# PWR_Gen.net
KiCad netlist of a schematic drawn in Altium Designer
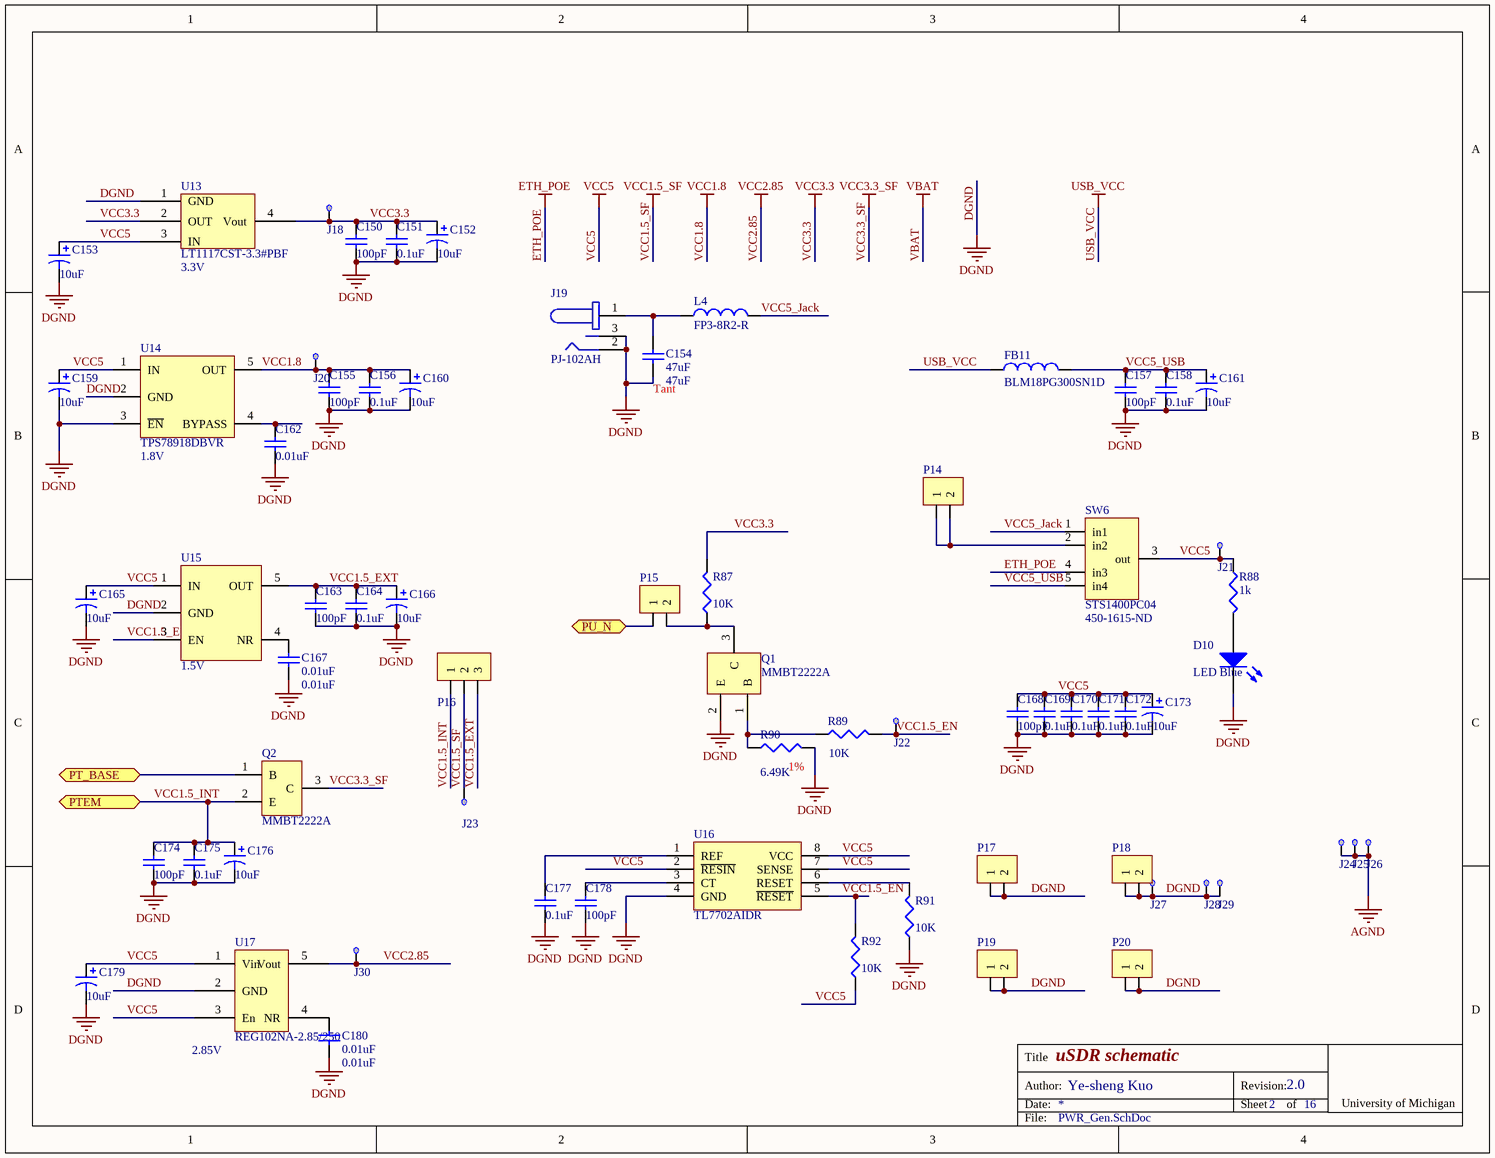
[diagram p0: PWR_Gen.SchDoc]

(export (version "E")
  (design (tool "Eeschema 10.0.6"))
  (components
    (comp (ref "C150")
      (value "100pF")
      (footprint "0402")
      (description "Capacitor (Semiconductor SIM Model)")
      (fields (field (name "PUBLISHER") "Altium Limited"))
      (libsource (lib "Miscellaneous Devices") (part "Cap Semi"))
    )
    (comp (ref "C151")
      (value "0.1uF")
      (footprint "0402")
      (description "Capacitor (Semiconductor SIM Model)")
      (fields (field (name "PUBLISHER") "Altium Limited"))
      (libsource (lib "Miscellaneous Devices") (part "Cap Semi"))
    )
    (comp (ref "C152")
      (value "10uF")
      (footprint "C0805")
      (description "Polarized Capacitor (Surface Mount)")
      (fields (field (name "PUBLISHER") "Altium Limited"))
      (libsource (lib "Miscellaneous Devices") (part "Cap Pol3"))
    )
    (comp (ref "C153")
      (value "10uF")
      (footprint "C0805")
      (description "Polarized Capacitor (Surface Mount)")
      (fields (field (name "PUBLISHER") "Altium Limited"))
      (libsource (lib "Miscellaneous Devices") (part "Cap Pol3"))
    )
    (comp (ref "C154")
      (value "47uF")
      (footprint "C1210")
      (description "Capacitor (Semiconductor SIM Model)")
      (fields (field (name "ALTIUM_VALUE") "47uF") (field (name "PUBLISHER") "Altium Limited"))
      (libsource (lib "Miscellaneous Devices") (part "Cap Semi"))
    )
    (comp (ref "C155")
      (value "100pF")
      (footprint "0402")
      (description "Capacitor (Semiconductor SIM Model)")
      (fields (field (name "PUBLISHER") "Altium Limited"))
      (libsource (lib "Miscellaneous Devices") (part "Cap Semi"))
    )
    (comp (ref "C156")
      (value "0.1uF")
      (footprint "0402")
      (description "Capacitor (Semiconductor SIM Model)")
      (fields (field (name "PUBLISHER") "Altium Limited"))
      (libsource (lib "Miscellaneous Devices") (part "Cap Semi"))
    )
    (comp (ref "C157")
      (value "100pF")
      (footprint "0402")
      (description "Capacitor (Semiconductor SIM Model)")
      (fields (field (name "PUBLISHER") "Altium Limited"))
      (libsource (lib "Miscellaneous Devices") (part "Cap Semi"))
    )
    (comp (ref "C158")
      (value "0.1uF")
      (footprint "0402")
      (description "Capacitor (Semiconductor SIM Model)")
      (fields (field (name "PUBLISHER") "Altium Limited"))
      (libsource (lib "Miscellaneous Devices") (part "Cap Semi"))
    )
    (comp (ref "C159")
      (value "10uF")
      (footprint "C0805")
      (description "Polarized Capacitor (Surface Mount)")
      (fields (field (name "PUBLISHER") "Altium Limited"))
      (libsource (lib "Miscellaneous Devices") (part "Cap Pol3"))
    )
    (comp (ref "C160")
      (value "10uF")
      (footprint "C0805")
      (description "Polarized Capacitor (Surface Mount)")
      (fields (field (name "PUBLISHER") "Altium Limited"))
      (libsource (lib "Miscellaneous Devices") (part "Cap Pol3"))
    )
    (comp (ref "C161")
      (value "10uF")
      (footprint "C0805")
      (description "Polarized Capacitor (Surface Mount)")
      (fields (field (name "PUBLISHER") "Altium Limited"))
      (libsource (lib "Miscellaneous Devices") (part "Cap Pol3"))
    )
    (comp (ref "C162")
      (value "0.01uF")
      (footprint "0402")
      (description "Capacitor (Semiconductor SIM Model)")
      (fields (field (name "PUBLISHER") "Altium Limited"))
      (libsource (lib "Miscellaneous Devices") (part "Cap Semi"))
    )
    (comp (ref "C163")
      (value "100pF")
      (footprint "0402")
      (description "Capacitor (Semiconductor SIM Model)")
      (fields (field (name "PUBLISHER") "Altium Limited"))
      (libsource (lib "Miscellaneous Devices") (part "Cap Semi"))
    )
    (comp (ref "C164")
      (value "0.1uF")
      (footprint "0402")
      (description "Capacitor (Semiconductor SIM Model)")
      (fields (field (name "PUBLISHER") "Altium Limited"))
      (libsource (lib "Miscellaneous Devices") (part "Cap Semi"))
    )
    (comp (ref "C165")
      (value "10uF")
      (footprint "C0805")
      (description "Polarized Capacitor (Surface Mount)")
      (fields (field (name "PUBLISHER") "Altium Limited"))
      (libsource (lib "Miscellaneous Devices") (part "Cap Pol3"))
    )
    (comp (ref "C166")
      (value "10uF")
      (footprint "C0805")
      (description "Polarized Capacitor (Surface Mount)")
      (fields (field (name "PUBLISHER") "Altium Limited"))
      (libsource (lib "Miscellaneous Devices") (part "Cap Pol3"))
    )
    (comp (ref "C167")
      (value "0.01uF")
      (footprint "0402")
      (description "Capacitor (Semiconductor SIM Model)")
      (fields (field (name "ALTIUM_VALUE") "0.01uF") (field (name "PUBLISHER") "Altium Limited"))
      (libsource (lib "Miscellaneous Devices") (part "Cap Semi"))
    )
    (comp (ref "C168")
      (value "100pF")
      (footprint "0402")
      (description "Capacitor (Semiconductor SIM Model)")
      (fields (field (name "PUBLISHER") "Altium Limited"))
      (libsource (lib "Miscellaneous Devices") (part "Cap Semi"))
    )
    (comp (ref "C169")
      (value "0.1uF")
      (footprint "0402")
      (description "Capacitor (Semiconductor SIM Model)")
      (fields (field (name "PUBLISHER") "Altium Limited"))
      (libsource (lib "Miscellaneous Devices") (part "Cap Semi"))
    )
    (comp (ref "C170")
      (value "0.1uF")
      (footprint "0402")
      (description "Capacitor (Semiconductor SIM Model)")
      (fields (field (name "PUBLISHER") "Altium Limited"))
      (libsource (lib "Miscellaneous Devices") (part "Cap Semi"))
    )
    (comp (ref "C171")
      (value "0.1uF")
      (footprint "0402")
      (description "Capacitor (Semiconductor SIM Model)")
      (fields (field (name "PUBLISHER") "Altium Limited"))
      (libsource (lib "Miscellaneous Devices") (part "Cap Semi"))
    )
    (comp (ref "C172")
      (value "0.1uF")
      (footprint "0402")
      (description "Capacitor (Semiconductor SIM Model)")
      (fields (field (name "PUBLISHER") "Altium Limited"))
      (libsource (lib "Miscellaneous Devices") (part "Cap Semi"))
    )
    (comp (ref "C173")
      (value "10uF")
      (footprint "C0805")
      (description "Polarized Capacitor (Surface Mount)")
      (fields (field (name "PUBLISHER") "Altium Limited"))
      (libsource (lib "Miscellaneous Devices") (part "Cap Pol3"))
    )
    (comp (ref "C174")
      (value "100pF")
      (footprint "0402")
      (description "Capacitor (Semiconductor SIM Model)")
      (fields (field (name "PUBLISHER") "Altium Limited"))
      (libsource (lib "Miscellaneous Devices") (part "Cap Semi"))
    )
    (comp (ref "C175")
      (value "0.1uF")
      (footprint "0402")
      (description "Capacitor (Semiconductor SIM Model)")
      (fields (field (name "PUBLISHER") "Altium Limited"))
      (libsource (lib "Miscellaneous Devices") (part "Cap Semi"))
    )
    (comp (ref "C176")
      (value "10uF")
      (footprint "C0805")
      (description "Polarized Capacitor (Surface Mount)")
      (fields (field (name "PUBLISHER") "Altium Limited"))
      (libsource (lib "Miscellaneous Devices") (part "Cap Pol3"))
    )
    (comp (ref "C177")
      (value "0.1uF")
      (footprint "0402")
      (description "Capacitor (Semiconductor SIM Model)")
      (fields (field (name "PUBLISHER") "Altium Limited"))
      (libsource (lib "Miscellaneous Devices") (part "Cap Semi"))
    )
    (comp (ref "C178")
      (value "100pF")
      (footprint "0402")
      (description "Capacitor (Semiconductor SIM Model)")
      (fields (field (name "PUBLISHER") "Altium Limited"))
      (libsource (lib "Miscellaneous Devices") (part "Cap Semi"))
    )
    (comp (ref "C179")
      (value "10uF")
      (footprint "C0805")
      (description "Polarized Capacitor (Surface Mount)")
      (fields (field (name "PUBLISHER") "Altium Limited"))
      (libsource (lib "Miscellaneous Devices") (part "Cap Pol3"))
    )
    (comp (ref "C180")
      (value "0.01uF")
      (footprint "0402")
      (description "Capacitor (Semiconductor SIM Model)")
      (fields (field (name "ALTIUM_VALUE") "0.01uF") (field (name "PUBLISHER") "Altium Limited"))
      (libsource (lib "Miscellaneous Devices") (part "Cap Semi"))
    )
    (comp (ref "D10")
      (value "LED Blue")
      (footprint "1608[0603]")
      (description "Typical RED, GREEN, YELLOW, AMBER GaAs LED")
      (fields (field (name "PUBLISHER") "Altium Limited"))
      (libsource (lib "Miscellaneous Devices") (part "LED2"))
    )
    (comp (ref "FB11")
      (value "BLM18PG300SN1D")
      (footprint "1608[0603]")
      (description "FERRITE CHIP 30 OHM 1000MA 0603")
      (libsource (lib "SDR") (part "Ferrite Bead"))
    )
    (comp (ref "J18")
      (value "5004")
      (footprint "TestPoint")
      (description "TEST POINT PC MINI .040\"D YELLOW")
      (libsource (lib "SDR") (part "TestPoint"))
    )
    (comp (ref "J19")
      (value "PJ-102AH")
      (footprint "PJ-102AH")
      (description "CONN PWR JACK 2.1X5.5MM HIGH CUR")
      (libsource (lib "SDR") (part "PJ-102AH"))
    )
    (comp (ref "J20")
      (value "5004")
      (footprint "TestPoint")
      (description "TEST POINT PC MINI .040\"D YELLOW")
      (libsource (lib "SDR") (part "TestPoint"))
    )
    (comp (ref "J21")
      (value "5004")
      (footprint "TestPoint")
      (description "TEST POINT PC MINI .040\"D YELLOW")
      (libsource (lib "SDR") (part "TestPoint"))
    )
    (comp (ref "J22")
      (value "5004")
      (footprint "TestPoint")
      (description "TEST POINT PC MINI .040\"D YELLOW")
      (libsource (lib "SDR") (part "TestPoint"))
    )
    (comp (ref "J23")
      (value "5004")
      (footprint "TestPoint")
      (description "TEST POINT PC MINI .040\"D YELLOW")
      (libsource (lib "SDR") (part "TestPoint"))
    )
    (comp (ref "J24")
      (value "5004")
      (footprint "TestPoint")
      (description "TEST POINT PC MINI .040\"D YELLOW")
      (libsource (lib "SDR") (part "TestPoint"))
    )
    (comp (ref "J25")
      (value "5004")
      (footprint "TestPoint")
      (description "TEST POINT PC MINI .040\"D YELLOW")
      (libsource (lib "SDR") (part "TestPoint"))
    )
    (comp (ref "J26")
      (value "5004")
      (footprint "TestPoint")
      (description "TEST POINT PC MINI .040\"D YELLOW")
      (libsource (lib "SDR") (part "TestPoint"))
    )
    (comp (ref "J27")
      (value "5004")
      (footprint "TestPoint")
      (description "TEST POINT PC MINI .040\"D YELLOW")
      (libsource (lib "SDR") (part "TestPoint"))
    )
    (comp (ref "J28")
      (value "5004")
      (footprint "TestPoint")
      (description "TEST POINT PC MINI .040\"D YELLOW")
      (libsource (lib "SDR") (part "TestPoint"))
    )
    (comp (ref "J29")
      (value "5004")
      (footprint "TestPoint")
      (description "TEST POINT PC MINI .040\"D YELLOW")
      (libsource (lib "SDR") (part "TestPoint"))
    )
    (comp (ref "J30")
      (value "5004")
      (footprint "TestPoint")
      (description "TEST POINT PC MINI .040\"D YELLOW")
      (libsource (lib "SDR") (part "TestPoint"))
    )
    (comp (ref "L4")
      (value "FP3-8R2-R")
      (footprint "FLAT-PAC")
      (fields (field (name "PUBLISHER") "Altium Limited"))
      (libsource (lib "Miscellaneous Devices") (part "Inductor"))
    )
    (comp (ref "P14")
      (value "1 x 2 header")
      (footprint "1x2 header")
      (description "100 mils standard header")
      (libsource (lib "SDR") (part "1 x 2 header"))
    )
    (comp (ref "P15")
      (value "1 x 2 header")
      (footprint "1x2 header")
      (description "100 mils standard header")
      (libsource (lib "SDR") (part "1 x 2 header"))
    )
    (comp (ref "P16")
      (value "1 x 3 header")
      (footprint "1x3 header")
      (description "100 mils standard header")
      (libsource (lib "SDR") (part "1 x 3 header"))
    )
    (comp (ref "P17")
      (value "1 x 2 header")
      (footprint "1x2 header")
      (description "100 mils standard header")
      (libsource (lib "SDR") (part "1 x 2 header"))
    )
    (comp (ref "P18")
      (value "1 x 2 header")
      (footprint "1x2 header")
      (description "100 mils standard header")
      (libsource (lib "SDR") (part "1 x 2 header"))
    )
    (comp (ref "P19")
      (value "1 x 2 header")
      (footprint "1x2 header")
      (description "100 mils standard header")
      (libsource (lib "SDR") (part "1 x 2 header"))
    )
    (comp (ref "P20")
      (value "1 x 2 header")
      (footprint "1x2 header")
      (description "100 mils standard header")
      (libsource (lib "SDR") (part "1 x 2 header"))
    )
    (comp (ref "Q1")
      (value "MMBT2222A")
      (footprint "SOT23-3N")
      (description "TRANSISTOR NPN GP 40V SOT23")
      (libsource (lib "SDR") (part "MMBT2222A"))
    )
    (comp (ref "Q2")
      (value "MMBT2222A")
      (footprint "SOT23-3N")
      (description "TRANSISTOR NPN GP 40V SOT23")
      (libsource (lib "SDR") (part "MMBT2222A"))
    )
    (comp (ref "R87")
      (value "10K")
      (footprint "0402")
      (description "Resistor")
      (fields (field (name "PUBLISHER") "Altium Limited"))
      (libsource (lib "Miscellaneous Devices") (part "Res3"))
    )
    (comp (ref "R88")
      (value "1k")
      (footprint "0402")
      (description "Resistor")
      (fields (field (name "Comment") "1K") (field (name "PUBLISHER") "Altium Limited"))
      (libsource (lib "Miscellaneous Devices") (part "Res3"))
    )
    (comp (ref "R89")
      (value "10K")
      (footprint "0402")
      (description "Resistor")
      (fields (field (name "PUBLISHER") "Altium Limited"))
      (libsource (lib "Miscellaneous Devices") (part "Res3"))
    )
    (comp (ref "R90")
      (value "6.49K")
      (footprint "0402")
      (description "Resistor")
      (fields (field (name "PUBLISHER") "Altium Limited"))
      (libsource (lib "Miscellaneous Devices") (part "Res3"))
    )
    (comp (ref "R91")
      (value "10K")
      (footprint "0402")
      (description "Resistor")
      (fields (field (name "PUBLISHER") "Altium Limited"))
      (libsource (lib "Miscellaneous Devices") (part "Res3"))
    )
    (comp (ref "R92")
      (value "10K")
      (footprint "0402")
      (description "Resistor")
      (fields (field (name "PUBLISHER") "Altium Limited"))
      (libsource (lib "Miscellaneous Devices") (part "Res3"))
    )
    (comp (ref "SW6")
      (value "STS1400PC04")
      (footprint "STS1400PC04")
      (description "Switch Slide 4 postions")
      (fields (field (name "SUPPLIER PART NUMBER 1") "450-1615-ND"))
      (libsource (lib "SDR") (part "STS1400PC04"))
    )
    (comp (ref "U13")
      (value "LT1117CST-3.3#PBF")
      (footprint "SOT223-4L")
      (description "IC REG LDO 3.3V SOT-223")
      (fields (field (name "ALTIUM_VALUE") "3.3V"))
      (libsource (lib "SDR") (part "LT1117-3.3"))
    )
    (comp (ref "U14")
      (value "TPS78918DBVR")
      (footprint "SOT23-5")
      (description "IC 1.8V 100MA LDO REG SOT-23-5")
      (fields (field (name "ALTIUM_VALUE") "1.8V"))
      (libsource (lib "SDR") (part "TPS789 LDO"))
    )
    (comp (ref "U15")
      (value "1.5V")
      (footprint "SOT23-5")
      (description "IC LDO REG 150MA 1.5V SOT23-5")
      (fields (field (name "Comment") "TPS73115DBVT"))
      (libsource (lib "SDR") (part "TPS731"))
    )
    (comp (ref "U16")
      (value "TL7702AIDR")
      (footprint "SOIC127P600X175-8N")
      (description "IC SUPPLY VOLT SUPERVISOR 8-SOIC")
      (libsource (lib "SDR") (part "TL7702AIDR"))
    )
    (comp (ref "U17")
      (value "REG102NA-2.85/250")
      (footprint "SOT23-5")
      (description "IC REG LDO 2.85V 250MA SOT23-5")
      (fields (field (name "ALTIUM_VALUE") "2.85V"))
      (libsource (lib "SDR") (part "REG102/103/104"))
    )
  )
  (nets
    (net (code "1") (name "/PT_BASE") (class "Default")
      (node (ref "Q2") (pin "1") (pinfunction "B_1") (pintype "passive"))
    )
    (net (code "2") (name "/PU_N") (class "Default")
      (node (ref "P15") (pin "1") (pinfunction "1_1") (pintype "passive"))
    )
    (net (code "3") (name "/VCC1.5_EN") (class "Default")
      (node (ref "J22") (pin "1") (pinfunction "TB_1") (pintype "passive"))
      (node (ref "R89") (pin "2") (pinfunction "2_2") (pintype "passive"))
      (node (ref "R92") (pin "2") (pinfunction "2_2") (pintype "passive"))
      (node (ref "U15") (pin "3") (pinfunction "EN_3") (pintype "passive"))
      (node (ref "U16") (pin "5") (pinfunction "~{RESET}_5") (pintype "passive"))
    )
    (net (code "4") (name "/VCC1.5_EXT") (class "Default")
      (node (ref "C163") (pin "2") (pinfunction "2_2") (pintype "passive"))
      (node (ref "C164") (pin "2") (pinfunction "2_2") (pintype "passive"))
      (node (ref "C166") (pin "1") (pinfunction "1_1") (pintype "passive"))
      (node (ref "P16") (pin "3") (pinfunction "3_3") (pintype "passive"))
      (node (ref "U15") (pin "5") (pinfunction "OUT_5") (pintype "passive"))
    )
    (net (code "5") (name "/VCC1.5_INT") (class "Default")
      (node (ref "C174") (pin "2") (pinfunction "2_2") (pintype "passive"))
      (node (ref "C175") (pin "2") (pinfunction "2_2") (pintype "passive"))
      (node (ref "C176") (pin "1") (pinfunction "1_1") (pintype "passive"))
      (node (ref "P16") (pin "1") (pinfunction "1_1") (pintype "passive"))
      (node (ref "Q2") (pin "2") (pinfunction "E_2") (pintype "passive"))
    )
    (net (code "6") (name "/VCC5_Jack") (class "Default")
      (node (ref "L4") (pin "2") (pinfunction "2_2") (pintype "passive"))
      (node (ref "SW6") (pin "1") (pinfunction "in1_1") (pintype "passive"))
    )
    (net (code "7") (name "/VCC5_USB") (class "Default")
      (node (ref "C157") (pin "2") (pinfunction "2_2") (pintype "passive"))
      (node (ref "C158") (pin "2") (pinfunction "2_2") (pintype "passive"))
      (node (ref "C161") (pin "1") (pinfunction "1_1") (pintype "passive"))
      (node (ref "FB11") (pin "2") (pinfunction "2_2") (pintype "passive"))
      (node (ref "SW6") (pin "5") (pinfunction "in4_5") (pintype "passive"))
    )
    (net (code "8") (name "AGND") (class "Default")
      (node (ref "J24") (pin "1") (pinfunction "TB_1") (pintype "passive"))
      (node (ref "J25") (pin "1") (pinfunction "TB_1") (pintype "passive"))
      (node (ref "J26") (pin "1") (pinfunction "TB_1") (pintype "passive"))
    )
    (net (code "9") (name "DGND") (class "Default")
      (node (ref "C150") (pin "1") (pinfunction "1_1") (pintype "passive"))
      (node (ref "C151") (pin "1") (pinfunction "1_1") (pintype "passive"))
      (node (ref "C152") (pin "2") (pinfunction "2_2") (pintype "passive"))
      (node (ref "C153") (pin "2") (pinfunction "2_2") (pintype "passive"))
      (node (ref "C154") (pin "1") (pinfunction "1_1") (pintype "passive"))
      (node (ref "C155") (pin "1") (pinfunction "1_1") (pintype "passive"))
      (node (ref "C156") (pin "1") (pinfunction "1_1") (pintype "passive"))
      (node (ref "C157") (pin "1") (pinfunction "1_1") (pintype "passive"))
      (node (ref "C158") (pin "1") (pinfunction "1_1") (pintype "passive"))
      (node (ref "C159") (pin "2") (pinfunction "2_2") (pintype "passive"))
      (node (ref "C160") (pin "2") (pinfunction "2_2") (pintype "passive"))
      (node (ref "C161") (pin "2") (pinfunction "2_2") (pintype "passive"))
      (node (ref "C162") (pin "1") (pinfunction "1_1") (pintype "passive"))
      (node (ref "C163") (pin "1") (pinfunction "1_1") (pintype "passive"))
      (node (ref "C164") (pin "1") (pinfunction "1_1") (pintype "passive"))
      (node (ref "C165") (pin "2") (pinfunction "2_2") (pintype "passive"))
      (node (ref "C166") (pin "2") (pinfunction "2_2") (pintype "passive"))
      (node (ref "C167") (pin "1") (pinfunction "1_1") (pintype "passive"))
      (node (ref "C168") (pin "1") (pinfunction "1_1") (pintype "passive"))
      (node (ref "C169") (pin "1") (pinfunction "1_1") (pintype "passive"))
      (node (ref "C170") (pin "1") (pinfunction "1_1") (pintype "passive"))
      (node (ref "C171") (pin "1") (pinfunction "1_1") (pintype "passive"))
      (node (ref "C172") (pin "1") (pinfunction "1_1") (pintype "passive"))
      (node (ref "C173") (pin "2") (pinfunction "2_2") (pintype "passive"))
      (node (ref "C174") (pin "1") (pinfunction "1_1") (pintype "passive"))
      (node (ref "C175") (pin "1") (pinfunction "1_1") (pintype "passive"))
      (node (ref "C176") (pin "2") (pinfunction "2_2") (pintype "passive"))
      (node (ref "C177") (pin "1") (pinfunction "1_1") (pintype "passive"))
      (node (ref "C178") (pin "1") (pinfunction "1_1") (pintype "passive"))
      (node (ref "C179") (pin "2") (pinfunction "2_2") (pintype "passive"))
      (node (ref "C180") (pin "1") (pinfunction "1_1") (pintype "passive"))
      (node (ref "D10") (pin "2") (pinfunction "K_2") (pintype "passive"))
      (node (ref "J19") (pin "2") (pintype "passive"))
      (node (ref "J19") (pin "3") (pintype "passive"))
      (node (ref "J27") (pin "1") (pinfunction "TB_1") (pintype "passive"))
      (node (ref "J28") (pin "1") (pinfunction "TB_1") (pintype "passive"))
      (node (ref "J29") (pin "1") (pinfunction "TB_1") (pintype "passive"))
      (node (ref "P17") (pin "1") (pinfunction "1_1") (pintype "passive"))
      (node (ref "P17") (pin "2") (pinfunction "2_2") (pintype "passive"))
      (node (ref "P18") (pin "1") (pinfunction "1_1") (pintype "passive"))
      (node (ref "P18") (pin "2") (pinfunction "2_2") (pintype "passive"))
      (node (ref "P19") (pin "1") (pinfunction "1_1") (pintype "passive"))
      (node (ref "P19") (pin "2") (pinfunction "2_2") (pintype "passive"))
      (node (ref "P20") (pin "1") (pinfunction "1_1") (pintype "passive"))
      (node (ref "P20") (pin "2") (pinfunction "2_2") (pintype "passive"))
      (node (ref "Q1") (pin "2") (pinfunction "E_2") (pintype "passive"))
      (node (ref "R90") (pin "2") (pinfunction "2_2") (pintype "passive"))
      (node (ref "R91") (pin "1") (pinfunction "1_1") (pintype "passive"))
      (node (ref "U13") (pin "1") (pinfunction "GND_1") (pintype "passive"))
      (node (ref "U14") (pin "2") (pinfunction "GND_2") (pintype "passive"))
      (node (ref "U14") (pin "3") (pinfunction "~{EN}_3") (pintype "passive"))
      (node (ref "U15") (pin "2") (pinfunction "GND_2") (pintype "passive"))
      (node (ref "U16") (pin "4") (pinfunction "GND_4") (pintype "passive"))
      (node (ref "U17") (pin "2") (pinfunction "GND_2") (pintype "passive"))
    )
    (net (code "10") (name "ETH_POE") (class "Default")
      (node (ref "SW6") (pin "4") (pinfunction "in3_4") (pintype "passive"))
    )
    (net (code "11") (name "Net-(C154-Pad2)") (class "Default")
      (node (ref "C154") (pin "2") (pinfunction "2_2") (pintype "passive"))
      (node (ref "J19") (pin "1") (pintype "passive"))
      (node (ref "L4") (pin "1") (pinfunction "1_1") (pintype "passive"))
    )
    (net (code "12") (name "Net-(D10-A)") (class "Default")
      (node (ref "D10") (pin "1") (pinfunction "A_1") (pintype "passive"))
      (node (ref "R88") (pin "2") (pinfunction "2_2") (pintype "passive"))
    )
    (net (code "13") (name "Net-(Q1-B)") (class "Default")
      (node (ref "Q1") (pin "1") (pinfunction "B_1") (pintype "passive"))
      (node (ref "R89") (pin "1") (pinfunction "1_1") (pintype "passive"))
      (node (ref "R90") (pin "1") (pinfunction "1_1") (pintype "passive"))
    )
    (net (code "14") (name "Net-(Q1-C)") (class "Default")
      (node (ref "P15") (pin "2") (pinfunction "2_2") (pintype "passive"))
      (node (ref "Q1") (pin "3") (pinfunction "C_3") (pintype "passive"))
      (node (ref "R87") (pin "1") (pinfunction "1_1") (pintype "passive"))
    )
    (net (code "15") (name "Net-(SW6-in2)") (class "Default")
      (node (ref "P14") (pin "1") (pinfunction "1_1") (pintype "passive"))
      (node (ref "P14") (pin "2") (pinfunction "2_2") (pintype "passive"))
      (node (ref "SW6") (pin "2") (pinfunction "in2_2") (pintype "passive"))
    )
    (net (code "16") (name "Net-(U14-BYPASS)") (class "Default")
      (node (ref "C162") (pin "2") (pinfunction "2_2") (pintype "passive"))
      (node (ref "U14") (pin "4") (pinfunction "BYPASS_4") (pintype "passive"))
    )
    (net (code "17") (name "Net-(U15-NR)") (class "Default")
      (node (ref "C167") (pin "2") (pinfunction "2_2") (pintype "passive"))
      (node (ref "U15") (pin "4") (pinfunction "NR_4") (pintype "passive"))
    )
    (net (code "18") (name "Net-(U16-CT)") (class "Default")
      (node (ref "C178") (pin "2") (pinfunction "2_2") (pintype "passive"))
      (node (ref "U16") (pin "3") (pinfunction "CT_3") (pintype "passive"))
    )
    (net (code "19") (name "Net-(U16-REF)") (class "Default")
      (node (ref "C177") (pin "2") (pinfunction "2_2") (pintype "passive"))
      (node (ref "U16") (pin "1") (pinfunction "REF_1") (pintype "passive"))
    )
    (net (code "20") (name "Net-(U16-RESET)") (class "Default")
      (node (ref "R91") (pin "2") (pinfunction "2_2") (pintype "passive"))
      (node (ref "U16") (pin "6") (pinfunction "RESET_6") (pintype "passive"))
    )
    (net (code "21") (name "Net-(U17-NR)") (class "Default")
      (node (ref "C180") (pin "2") (pinfunction "2_2") (pintype "passive"))
      (node (ref "U17") (pin "4") (pinfunction "NR_4") (pintype "passive"))
    )
    (net (code "22") (name "USB_VCC") (class "Default")
      (node (ref "FB11") (pin "1") (pinfunction "1_1") (pintype "passive"))
    )
    (net (code "24") (name "VCC1.5_SF") (class "Default")
      (node (ref "J23") (pin "1") (pinfunction "TB_1") (pintype "passive"))
      (node (ref "P16") (pin "2") (pinfunction "2_2") (pintype "passive"))
    )
    (net (code "25") (name "VCC1.8") (class "Default")
      (node (ref "C155") (pin "2") (pinfunction "2_2") (pintype "passive"))
      (node (ref "C156") (pin "2") (pinfunction "2_2") (pintype "passive"))
      (node (ref "C160") (pin "1") (pinfunction "1_1") (pintype "passive"))
      (node (ref "J20") (pin "1") (pinfunction "TB_1") (pintype "passive"))
      (node (ref "U14") (pin "5") (pinfunction "OUT_5") (pintype "passive"))
    )
    (net (code "26") (name "VCC2.85") (class "Default")
      (node (ref "J30") (pin "1") (pinfunction "TB_1") (pintype "passive"))
      (node (ref "U17") (pin "5") (pinfunction "Vout_5") (pintype "passive"))
    )
    (net (code "27") (name "VCC3.3") (class "Default")
      (node (ref "C150") (pin "2") (pinfunction "2_2") (pintype "passive"))
      (node (ref "C151") (pin "2") (pinfunction "2_2") (pintype "passive"))
      (node (ref "C152") (pin "1") (pinfunction "1_1") (pintype "passive"))
      (node (ref "J18") (pin "1") (pinfunction "TB_1") (pintype "passive"))
      (node (ref "R87") (pin "2") (pinfunction "2_2") (pintype "passive"))
      (node (ref "U13") (pin "2") (pinfunction "OUT_2") (pintype "passive"))
      (node (ref "U13") (pin "4") (pinfunction "Vout_4") (pintype "passive"))
    )
    (net (code "28") (name "VCC3.3_SF") (class "Default")
      (node (ref "Q2") (pin "3") (pinfunction "C_3") (pintype "passive"))
    )
    (net (code "29") (name "VCC5") (class "Default")
      (node (ref "C153") (pin "1") (pinfunction "1_1") (pintype "passive"))
      (node (ref "C159") (pin "1") (pinfunction "1_1") (pintype "passive"))
      (node (ref "C165") (pin "1") (pinfunction "1_1") (pintype "passive"))
      (node (ref "C168") (pin "2") (pinfunction "2_2") (pintype "passive"))
      (node (ref "C169") (pin "2") (pinfunction "2_2") (pintype "passive"))
      (node (ref "C170") (pin "2") (pinfunction "2_2") (pintype "passive"))
      (node (ref "C171") (pin "2") (pinfunction "2_2") (pintype "passive"))
      (node (ref "C172") (pin "2") (pinfunction "2_2") (pintype "passive"))
      (node (ref "C173") (pin "1") (pinfunction "1_1") (pintype "passive"))
      (node (ref "C179") (pin "1") (pinfunction "1_1") (pintype "passive"))
      (node (ref "J21") (pin "1") (pinfunction "TB_1") (pintype "passive"))
      (node (ref "R88") (pin "1") (pinfunction "1_1") (pintype "passive"))
      (node (ref "R92") (pin "1") (pinfunction "1_1") (pintype "passive"))
      (node (ref "SW6") (pin "3") (pinfunction "out_3") (pintype "passive"))
      (node (ref "U13") (pin "3") (pinfunction "IN_3") (pintype "passive"))
      (node (ref "U14") (pin "1") (pinfunction "IN_1") (pintype "passive"))
      (node (ref "U15") (pin "1") (pinfunction "IN_1") (pintype "passive"))
      (node (ref "U16") (pin "2") (pinfunction "~{RESIN}_2") (pintype "passive"))
      (node (ref "U16") (pin "7") (pinfunction "SENSE_7") (pintype "passive"))
      (node (ref "U16") (pin "8") (pinfunction "VCC_8") (pintype "passive"))
      (node (ref "U17") (pin "1") (pinfunction "Vin_1") (pintype "passive"))
      (node (ref "U17") (pin "3") (pinfunction "En_3") (pintype "passive"))
    )
  )
)
